# brain.net
KiCad netlist of a schematic drawn in Altium Designer
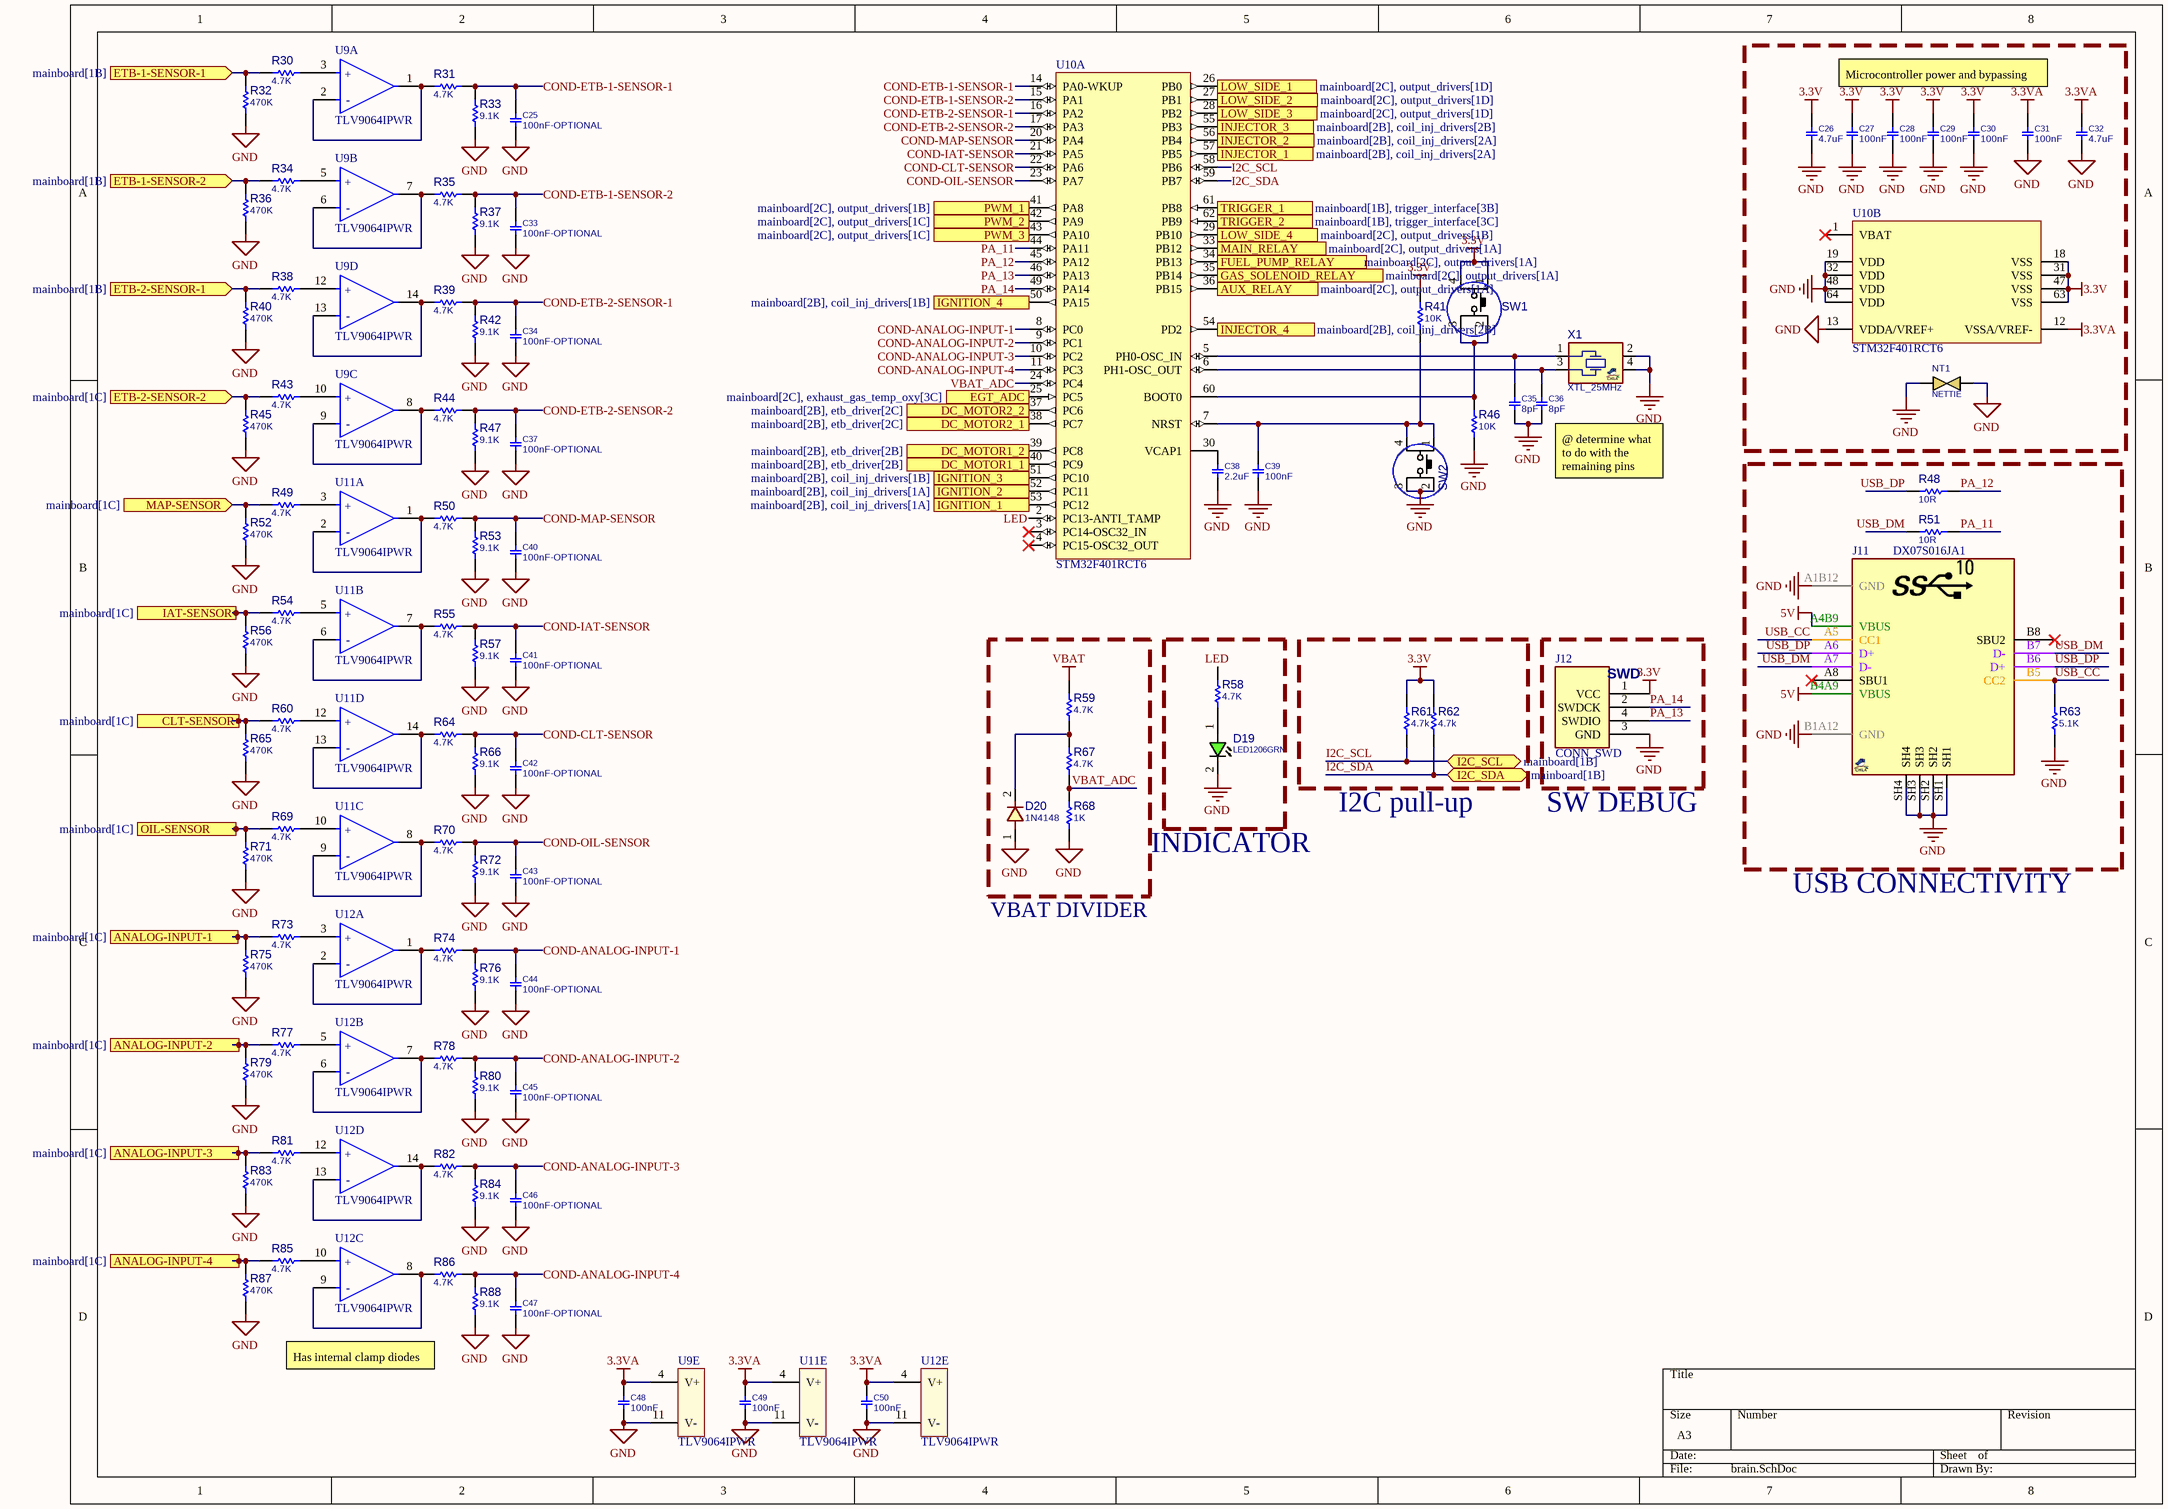
[diagram p0: brain.SchDoc]

(export (version "E")
  (design (tool "Eeschema 10.0.6"))
  (components
    (comp (ref "C25")
      (value "100nF-OPTIONAL")
      (footprint "C0805")
      (description "CAP, MLCC")
      (fields (field (name "MANF_P#") "MANF_PART#") (field (name "MANF") "Murata"))
      (libsource (lib "passive_smd") (part "CAP_SMD_MLCC"))
    )
    (comp (ref "C26")
      (value "4.7uF")
      (footprint "C0805")
      (description "CAP, MLCC")
      (fields (field (name "MANF_P#") "MANF_PART#") (field (name "MANF") "Murata"))
      (libsource (lib "passive_smd") (part "CAP_SMD_MLCC"))
    )
    (comp (ref "C27")
      (value "100nF")
      (footprint "C0805")
      (description "CAP, MLCC")
      (fields (field (name "MANF_P#") "MANF_PART#") (field (name "MANF") "Murata"))
      (libsource (lib "passive_smd") (part "CAP_SMD_MLCC"))
    )
    (comp (ref "C28")
      (value "100nF")
      (footprint "C0805")
      (description "CAP, MLCC")
      (fields (field (name "MANF_P#") "MANF_PART#") (field (name "MANF") "Murata"))
      (libsource (lib "passive_smd") (part "CAP_SMD_MLCC"))
    )
    (comp (ref "C29")
      (value "100nF")
      (footprint "C0805")
      (description "CAP, MLCC")
      (fields (field (name "MANF_P#") "MANF_PART#") (field (name "MANF") "Murata"))
      (libsource (lib "passive_smd") (part "CAP_SMD_MLCC"))
    )
    (comp (ref "C30")
      (value "100nF")
      (footprint "C0805")
      (description "CAP, MLCC")
      (fields (field (name "MANF_P#") "MANF_PART#") (field (name "MANF") "Murata"))
      (libsource (lib "passive_smd") (part "CAP_SMD_MLCC"))
    )
    (comp (ref "C31")
      (value "100nF")
      (footprint "C0805")
      (description "CAP, MLCC")
      (fields (field (name "MANF_P#") "MANF_PART#") (field (name "MANF") "Murata"))
      (libsource (lib "passive_smd") (part "CAP_SMD_MLCC"))
    )
    (comp (ref "C32")
      (value "4.7uF")
      (footprint "C0805")
      (description "CAP, MLCC")
      (fields (field (name "MANF_P#") "MANF_PART#") (field (name "MANF") "Murata"))
      (libsource (lib "passive_smd") (part "CAP_SMD_MLCC"))
    )
    (comp (ref "C33")
      (value "100nF-OPTIONAL")
      (footprint "C0805")
      (description "CAP, MLCC")
      (fields (field (name "MANF_P#") "MANF_PART#") (field (name "MANF") "Murata"))
      (libsource (lib "passive_smd") (part "CAP_SMD_MLCC"))
    )
    (comp (ref "C34")
      (value "100nF-OPTIONAL")
      (footprint "C0805")
      (description "CAP, MLCC")
      (fields (field (name "MANF_P#") "MANF_PART#") (field (name "MANF") "Murata"))
      (libsource (lib "passive_smd") (part "CAP_SMD_MLCC"))
    )
    (comp (ref "C35")
      (value "8pF")
      (footprint "C0805")
      (description "CAP, MLCC")
      (fields (field (name "MANF_P#") "MANF_PART#") (field (name "MANF") "Murata"))
      (libsource (lib "passive_smd") (part "CAP_SMD_MLCC"))
    )
    (comp (ref "C36")
      (value "8pF")
      (footprint "C0805")
      (description "CAP, MLCC")
      (fields (field (name "MANF_P#") "MANF_PART#") (field (name "MANF") "Murata"))
      (libsource (lib "passive_smd") (part "CAP_SMD_MLCC"))
    )
    (comp (ref "C37")
      (value "100nF-OPTIONAL")
      (footprint "C0805")
      (description "CAP, MLCC")
      (fields (field (name "MANF_P#") "MANF_PART#") (field (name "MANF") "Murata"))
      (libsource (lib "passive_smd") (part "CAP_SMD_MLCC"))
    )
    (comp (ref "C38")
      (value "2.2uF")
      (footprint "C0805")
      (description "CAP, MLCC")
      (fields (field (name "MANF_P#") "MANF_PART#") (field (name "MANF") "Murata"))
      (libsource (lib "passive_smd") (part "CAP_SMD_MLCC"))
    )
    (comp (ref "C39")
      (value "100nF")
      (footprint "C0805")
      (description "CAP, MLCC")
      (fields (field (name "MANF_P#") "MANF_PART#") (field (name "MANF") "Murata"))
      (libsource (lib "passive_smd") (part "CAP_SMD_MLCC"))
    )
    (comp (ref "C40")
      (value "100nF-OPTIONAL")
      (footprint "C0805")
      (description "CAP, MLCC")
      (fields (field (name "MANF_P#") "MANF_PART#") (field (name "MANF") "Murata"))
      (libsource (lib "passive_smd") (part "CAP_SMD_MLCC"))
    )
    (comp (ref "C41")
      (value "100nF-OPTIONAL")
      (footprint "C0805")
      (description "CAP, MLCC")
      (fields (field (name "MANF_P#") "MANF_PART#") (field (name "MANF") "Murata"))
      (libsource (lib "passive_smd") (part "CAP_SMD_MLCC"))
    )
    (comp (ref "C42")
      (value "100nF-OPTIONAL")
      (footprint "C0805")
      (description "CAP, MLCC")
      (fields (field (name "MANF_P#") "MANF_PART#") (field (name "MANF") "Murata"))
      (libsource (lib "passive_smd") (part "CAP_SMD_MLCC"))
    )
    (comp (ref "C43")
      (value "100nF-OPTIONAL")
      (footprint "C0805")
      (description "CAP, MLCC")
      (fields (field (name "MANF_P#") "MANF_PART#") (field (name "MANF") "Murata"))
      (libsource (lib "passive_smd") (part "CAP_SMD_MLCC"))
    )
    (comp (ref "C44")
      (value "100nF-OPTIONAL")
      (footprint "C0805")
      (description "CAP, MLCC")
      (fields (field (name "MANF_P#") "MANF_PART#") (field (name "MANF") "Murata"))
      (libsource (lib "passive_smd") (part "CAP_SMD_MLCC"))
    )
    (comp (ref "C45")
      (value "100nF-OPTIONAL")
      (footprint "C0805")
      (description "CAP, MLCC")
      (fields (field (name "MANF_P#") "MANF_PART#") (field (name "MANF") "Murata"))
      (libsource (lib "passive_smd") (part "CAP_SMD_MLCC"))
    )
    (comp (ref "C46")
      (value "100nF-OPTIONAL")
      (footprint "C0805")
      (description "CAP, MLCC")
      (fields (field (name "MANF_P#") "MANF_PART#") (field (name "MANF") "Murata"))
      (libsource (lib "passive_smd") (part "CAP_SMD_MLCC"))
    )
    (comp (ref "C47")
      (value "100nF-OPTIONAL")
      (footprint "C0805")
      (description "CAP, MLCC")
      (fields (field (name "MANF_P#") "MANF_PART#") (field (name "MANF") "Murata"))
      (libsource (lib "passive_smd") (part "CAP_SMD_MLCC"))
    )
    (comp (ref "C48")
      (value "100nF")
      (footprint "C0805")
      (description "CAP, MLCC")
      (fields (field (name "MANF_P#") "MANF_PART#") (field (name "MANF") "Murata"))
      (libsource (lib "passive_smd") (part "CAP_SMD_MLCC"))
    )
    (comp (ref "C49")
      (value "100nF")
      (footprint "C0805")
      (description "CAP, MLCC")
      (fields (field (name "MANF_P#") "MANF_PART#") (field (name "MANF") "Murata"))
      (libsource (lib "passive_smd") (part "CAP_SMD_MLCC"))
    )
    (comp (ref "C50")
      (value "100nF")
      (footprint "C0805")
      (description "CAP, MLCC")
      (fields (field (name "MANF_P#") "MANF_PART#") (field (name "MANF") "Murata"))
      (libsource (lib "passive_smd") (part "CAP_SMD_MLCC"))
    )
    (comp (ref "D19")
      (value "LED1206GRN")
      (footprint "LED1206GRN")
      (description "LED, SMD, 1206, GREEN")
      (libsource (lib "led(diode)") (part "LED_SMD_1206_GRN"))
    )
    (comp (ref "D20")
      (value "1N4148")
      (footprint "D_SOD80")
      (description "DIODE, FAST SWTICHING, 0.3A, 0.5W")
      (fields (field (name "MANF") "MANF"))
      (libsource (lib "diode") (part "DIODE_SMD_1N4148_SOD80"))
    )
    (comp (ref "J11")
      (value "DX07S016JA1")
      (footprint "USBC_SMD_16_DX07S016JA1")
      (description "CONN, USB, Type C, USB 2.0, Right-Angle, SMD")
      (fields (field (name "MANF") "JAE") (field (name "MANF_P#") "DX07S016JA1R1500"))
      (libsource (lib "conn_usbc") (part "CONN_USBC_SMD_16_DX07S016JA1"))
    )
    (comp (ref "J12")
      (value "CONN_SWD")
      (footprint "WF_4")
      (description "CONN, SWD, ST")
      (libsource (lib "conn_program") (part "CONN_SWD"))
    )
    (comp (ref "NT1")
      (value "NETTIE")
      (footprint "NETTIE_40X50")
      (description "NET TIE")
      (libsource (lib "test-tp_jumper") (part "NETTIE_40X50"))
    )
    (comp (ref "R30")
      (value "4.7K")
      (footprint "R0805")
      (description "RESISTOR, SMD")
      (libsource (lib "passive_smd") (part "RES_SMD"))
    )
    (comp (ref "R31")
      (value "4.7K")
      (footprint "R0805")
      (description "RESISTOR, SMD")
      (libsource (lib "passive_smd") (part "RES_SMD"))
    )
    (comp (ref "R32")
      (value "470K")
      (footprint "R0805")
      (description "RESISTOR, SMD")
      (libsource (lib "passive_smd") (part "RES_SMD"))
    )
    (comp (ref "R33")
      (value "9.1K")
      (footprint "R0805")
      (description "RESISTOR, SMD")
      (libsource (lib "passive_smd") (part "RES_SMD"))
    )
    (comp (ref "R34")
      (value "4.7K")
      (footprint "R0805")
      (description "RESISTOR, SMD")
      (libsource (lib "passive_smd") (part "RES_SMD"))
    )
    (comp (ref "R35")
      (value "4.7K")
      (footprint "R0805")
      (description "RESISTOR, SMD")
      (libsource (lib "passive_smd") (part "RES_SMD"))
    )
    (comp (ref "R36")
      (value "470K")
      (footprint "R0805")
      (description "RESISTOR, SMD")
      (libsource (lib "passive_smd") (part "RES_SMD"))
    )
    (comp (ref "R37")
      (value "9.1K")
      (footprint "R0805")
      (description "RESISTOR, SMD")
      (libsource (lib "passive_smd") (part "RES_SMD"))
    )
    (comp (ref "R38")
      (value "4.7K")
      (footprint "R0805")
      (description "RESISTOR, SMD")
      (libsource (lib "passive_smd") (part "RES_SMD"))
    )
    (comp (ref "R39")
      (value "4.7K")
      (footprint "R0805")
      (description "RESISTOR, SMD")
      (libsource (lib "passive_smd") (part "RES_SMD"))
    )
    (comp (ref "R40")
      (value "470K")
      (footprint "R0805")
      (description "RESISTOR, SMD")
      (libsource (lib "passive_smd") (part "RES_SMD"))
    )
    (comp (ref "R41")
      (value "10K")
      (footprint "R0805")
      (description "RESISTOR, SMD")
      (libsource (lib "passive_smd") (part "RES_SMD"))
    )
    (comp (ref "R42")
      (value "9.1K")
      (footprint "R0805")
      (description "RESISTOR, SMD")
      (libsource (lib "passive_smd") (part "RES_SMD"))
    )
    (comp (ref "R43")
      (value "4.7K")
      (footprint "R0805")
      (description "RESISTOR, SMD")
      (libsource (lib "passive_smd") (part "RES_SMD"))
    )
    (comp (ref "R44")
      (value "4.7K")
      (footprint "R0805")
      (description "RESISTOR, SMD")
      (libsource (lib "passive_smd") (part "RES_SMD"))
    )
    (comp (ref "R45")
      (value "470K")
      (footprint "R0805")
      (description "RESISTOR, SMD")
      (libsource (lib "passive_smd") (part "RES_SMD"))
    )
    (comp (ref "R46")
      (value "10K")
      (footprint "R0805")
      (description "RESISTOR, SMD")
      (libsource (lib "passive_smd") (part "RES_SMD"))
    )
    (comp (ref "R47")
      (value "9.1K")
      (footprint "R0805")
      (description "RESISTOR, SMD")
      (libsource (lib "passive_smd") (part "RES_SMD"))
    )
    (comp (ref "R48")
      (value "10R")
      (footprint "R0805")
      (description "RESISTOR, SMD")
      (libsource (lib "passive_smd") (part "RES_SMD_0805"))
    )
    (comp (ref "R49")
      (value "4.7K")
      (footprint "R0805")
      (description "RESISTOR, SMD")
      (libsource (lib "passive_smd") (part "RES_SMD"))
    )
    (comp (ref "R50")
      (value "4.7K")
      (footprint "R0805")
      (description "RESISTOR, SMD")
      (libsource (lib "passive_smd") (part "RES_SMD"))
    )
    (comp (ref "R51")
      (value "10R")
      (footprint "R0805")
      (description "RESISTOR, SMD")
      (libsource (lib "passive_smd") (part "RES_SMD_0805"))
    )
    (comp (ref "R52")
      (value "470K")
      (footprint "R0805")
      (description "RESISTOR, SMD")
      (libsource (lib "passive_smd") (part "RES_SMD"))
    )
    (comp (ref "R53")
      (value "9.1K")
      (footprint "R0805")
      (description "RESISTOR, SMD")
      (libsource (lib "passive_smd") (part "RES_SMD"))
    )
    (comp (ref "R54")
      (value "4.7K")
      (footprint "R0805")
      (description "RESISTOR, SMD")
      (libsource (lib "passive_smd") (part "RES_SMD"))
    )
    (comp (ref "R55")
      (value "4.7K")
      (footprint "R0805")
      (description "RESISTOR, SMD")
      (libsource (lib "passive_smd") (part "RES_SMD"))
    )
    (comp (ref "R56")
      (value "470K")
      (footprint "R0805")
      (description "RESISTOR, SMD")
      (libsource (lib "passive_smd") (part "RES_SMD"))
    )
    (comp (ref "R57")
      (value "9.1K")
      (footprint "R0805")
      (description "RESISTOR, SMD")
      (libsource (lib "passive_smd") (part "RES_SMD"))
    )
    (comp (ref "R58")
      (value "4.7K")
      (footprint "R0805")
      (description "RESISTOR, SMD")
      (libsource (lib "passive_smd") (part "RES_SMD"))
    )
    (comp (ref "R59")
      (value "4.7K")
      (footprint "R0805")
      (description "RESISTOR, SMD")
      (libsource (lib "passive_smd") (part "RES_SMD"))
    )
    (comp (ref "R60")
      (value "4.7K")
      (footprint "R0805")
      (description "RESISTOR, SMD")
      (libsource (lib "passive_smd") (part "RES_SMD"))
    )
    (comp (ref "R61")
      (value "4.7k")
      (footprint "R0805")
      (description "RESISTOR, SMD")
      (libsource (lib "passive_smd") (part "RES_SMD"))
    )
    (comp (ref "R62")
      (value "4.7k")
      (footprint "R0805")
      (description "RESISTOR, SMD")
      (libsource (lib "passive_smd") (part "RES_SMD"))
    )
    (comp (ref "R63")
      (value "5.1K")
      (footprint "R1206")
      (description "RESISTOR, SMD")
      (libsource (lib "passive_smd") (part "RES_SMD_1206"))
    )
    (comp (ref "R64")
      (value "4.7K")
      (footprint "R0805")
      (description "RESISTOR, SMD")
      (libsource (lib "passive_smd") (part "RES_SMD"))
    )
    (comp (ref "R65")
      (value "470K")
      (footprint "R0805")
      (description "RESISTOR, SMD")
      (libsource (lib "passive_smd") (part "RES_SMD"))
    )
    (comp (ref "R66")
      (value "9.1K")
      (footprint "R0805")
      (description "RESISTOR, SMD")
      (libsource (lib "passive_smd") (part "RES_SMD"))
    )
    (comp (ref "R67")
      (value "4.7K")
      (footprint "R0805")
      (description "RESISTOR, SMD")
      (libsource (lib "passive_smd") (part "RES_SMD"))
    )
    (comp (ref "R68")
      (value "1K")
      (footprint "R0805")
      (description "RESISTOR, SMD")
      (libsource (lib "passive_smd") (part "RES_SMD"))
    )
    (comp (ref "R69")
      (value "4.7K")
      (footprint "R0805")
      (description "RESISTOR, SMD")
      (libsource (lib "passive_smd") (part "RES_SMD"))
    )
    (comp (ref "R70")
      (value "4.7K")
      (footprint "R0805")
      (description "RESISTOR, SMD")
      (libsource (lib "passive_smd") (part "RES_SMD"))
    )
    (comp (ref "R71")
      (value "470K")
      (footprint "R0805")
      (description "RESISTOR, SMD")
      (libsource (lib "passive_smd") (part "RES_SMD"))
    )
    (comp (ref "R72")
      (value "9.1K")
      (footprint "R0805")
      (description "RESISTOR, SMD")
      (libsource (lib "passive_smd") (part "RES_SMD"))
    )
    (comp (ref "R73")
      (value "4.7K")
      (footprint "R0805")
      (description "RESISTOR, SMD")
      (libsource (lib "passive_smd") (part "RES_SMD"))
    )
    (comp (ref "R74")
      (value "4.7K")
      (footprint "R0805")
      (description "RESISTOR, SMD")
      (libsource (lib "passive_smd") (part "RES_SMD"))
    )
    (comp (ref "R75")
      (value "470K")
      (footprint "R0805")
      (description "RESISTOR, SMD")
      (libsource (lib "passive_smd") (part "RES_SMD"))
    )
    (comp (ref "R76")
      (value "9.1K")
      (footprint "R0805")
      (description "RESISTOR, SMD")
      (libsource (lib "passive_smd") (part "RES_SMD"))
    )
    (comp (ref "R77")
      (value "4.7K")
      (footprint "R0805")
      (description "RESISTOR, SMD")
      (libsource (lib "passive_smd") (part "RES_SMD"))
    )
    (comp (ref "R78")
      (value "4.7K")
      (footprint "R0805")
      (description "RESISTOR, SMD")
      (libsource (lib "passive_smd") (part "RES_SMD"))
    )
    (comp (ref "R79")
      (value "470K")
      (footprint "R0805")
      (description "RESISTOR, SMD")
      (libsource (lib "passive_smd") (part "RES_SMD"))
    )
    (comp (ref "R80")
      (value "9.1K")
      (footprint "R0805")
      (description "RESISTOR, SMD")
      (libsource (lib "passive_smd") (part "RES_SMD"))
    )
    (comp (ref "R81")
      (value "4.7K")
      (footprint "R0805")
      (description "RESISTOR, SMD")
      (libsource (lib "passive_smd") (part "RES_SMD"))
    )
    (comp (ref "R82")
      (value "4.7K")
      (footprint "R0805")
      (description "RESISTOR, SMD")
      (libsource (lib "passive_smd") (part "RES_SMD"))
    )
    (comp (ref "R83")
      (value "470K")
      (footprint "R0805")
      (description "RESISTOR, SMD")
      (libsource (lib "passive_smd") (part "RES_SMD"))
    )
    (comp (ref "R84")
      (value "9.1K")
      (footprint "R0805")
      (description "RESISTOR, SMD")
      (libsource (lib "passive_smd") (part "RES_SMD"))
    )
    (comp (ref "R85")
      (value "4.7K")
      (footprint "R0805")
      (description "RESISTOR, SMD")
      (libsource (lib "passive_smd") (part "RES_SMD"))
    )
    (comp (ref "R86")
      (value "4.7K")
      (footprint "R0805")
      (description "RESISTOR, SMD")
      (libsource (lib "passive_smd") (part "RES_SMD"))
    )
    (comp (ref "R87")
      (value "470K")
      (footprint "R0805")
      (description "RESISTOR, SMD")
      (libsource (lib "passive_smd") (part "RES_SMD"))
    )
    (comp (ref "R88")
      (value "9.1K")
      (footprint "R0805")
      (description "RESISTOR, SMD")
      (libsource (lib "passive_smd") (part "RES_SMD"))
    )
    (comp (ref "SW1")
      (value "PUSHBUTTON")
      (footprint "SWPBS_SPDT_5X5X1")
      (description "SWITCH, PUSH BUTTON, TACTILE, SMD, SPDT, 5X5MM")
      (fields (field (name "MANF") "CHINA") (field (name "MANF_P#") "PTS526SM15SMTR2LFS"))
      (libsource (lib "switch_tact_PUSHB") (part "SWPBS_SPDT_5X5PTS"))
    )
    (comp (ref "SW2")
      (value "PUSHBUTTON")
      (footprint "SWPBS_SPDT_5X5X1")
      (description "SWITCH, PUSH BUTTON, TACTILE, SMD, SPDT, 5X5MM")
      (fields (field (name "MANF") "CHINA") (field (name "MANF_P#") "PTS526SM15SMTR2LFS"))
      (libsource (lib "switch_tact_PUSHB") (part "SWPBS_SPDT_5X5PTS"))
    )
    (comp (ref "U9")
      (value "TLV9064IPWR")
      (footprint "TTSOP-14")
      (description "IC CMOS 4 CIRCUIT 14TSSOP")
      (libsource (lib "alib") (part "TLV9064"))
    )
    (comp (ref "U10")
      (value "STM32F401RCT6")
      (footprint "STM-LQFP64_L")
      (fields (field (name "MANUFACTURER") "STMicroelectronics"))
      (libsource (lib "Alib") (part "STM32F401RCT6"))
    )
    (comp (ref "U11")
      (value "TLV9064IPWR")
      (footprint "TTSOP-14")
      (description "IC CMOS 4 CIRCUIT 14TSSOP")
      (libsource (lib "alib") (part "TLV9064"))
    )
    (comp (ref "U12")
      (value "TLV9064IPWR")
      (footprint "TTSOP-14")
      (description "IC CMOS 4 CIRCUIT 14TSSOP")
      (libsource (lib "alib") (part "TLV9064"))
    )
    (comp (ref "X1")
      (value "XTL_25MHz")
      (footprint "XTL_4_3225")
      (description "CRYSTAL 25.00 MHZ 4pF, 10PPM")
      (fields (field (name "MANF") "ABRACON") (field (name "MANF_P#") "ABM8W-25.0000MHZ-4-D1X-T3"))
      (libsource (lib "crystal") (part "XTL_4_25MHZ_3225A_2"))
    )
  )
  (nets
    (net (code "1") (name "/ANALOG-INPUT-1") (class "Default")
      (node (ref "R73") (pin "2") (pinfunction "2_2") (pintype "passive"))
      (node (ref "R75") (pin "1") (pinfunction "1_1") (pintype "passive"))
    )
    (net (code "2") (name "/ANALOG-INPUT-2") (class "Default")
      (node (ref "R77") (pin "2") (pinfunction "2_2") (pintype "passive"))
      (node (ref "R79") (pin "1") (pinfunction "1_1") (pintype "passive"))
    )
    (net (code "3") (name "/ANALOG-INPUT-3") (class "Default")
      (node (ref "R81") (pin "2") (pinfunction "2_2") (pintype "passive"))
      (node (ref "R83") (pin "1") (pinfunction "1_1") (pintype "passive"))
    )
    (net (code "4") (name "/ANALOG-INPUT-4") (class "Default")
      (node (ref "R85") (pin "2") (pinfunction "2_2") (pintype "passive"))
      (node (ref "R87") (pin "1") (pinfunction "1_1") (pintype "passive"))
    )
    (net (code "5") (name "/AUX_RELAY") (class "Default")
      (node (ref "U10") (pin "36") (pinfunction "PB15_36") (pintype "output"))
    )
    (net (code "6") (name "/CLT-SENSOR") (class "Default")
      (node (ref "R60") (pin "2") (pinfunction "2_2") (pintype "passive"))
      (node (ref "R65") (pin "1") (pinfunction "1_1") (pintype "passive"))
    )
    (net (code "7") (name "/COND-ANALOG-INPUT-1") (class "Default")
      (node (ref "C44") (pin "2") (pinfunction "2_2") (pintype "passive"))
      (node (ref "R74") (pin "1") (pinfunction "1_1") (pintype "passive"))
      (node (ref "R76") (pin "1") (pinfunction "1_1") (pintype "passive"))
      (node (ref "U10") (pin "8") (pinfunction "PC0_8") (pintype "bidirectional"))
    )
    (net (code "8") (name "/COND-ANALOG-INPUT-2") (class "Default")
      (node (ref "C45") (pin "2") (pinfunction "2_2") (pintype "passive"))
      (node (ref "R78") (pin "1") (pinfunction "1_1") (pintype "passive"))
      (node (ref "R80") (pin "1") (pinfunction "1_1") (pintype "passive"))
      (node (ref "U10") (pin "9") (pinfunction "PC1_9") (pintype "bidirectional"))
    )
    (net (code "9") (name "/COND-ANALOG-INPUT-3") (class "Default")
      (node (ref "C46") (pin "2") (pinfunction "2_2") (pintype "passive"))
      (node (ref "R82") (pin "1") (pinfunction "1_1") (pintype "passive"))
      (node (ref "R84") (pin "1") (pinfunction "1_1") (pintype "passive"))
      (node (ref "U10") (pin "10") (pinfunction "PC2_10") (pintype "bidirectional"))
    )
    (net (code "10") (name "/COND-ANALOG-INPUT-4") (class "Default")
      (node (ref "C47") (pin "2") (pinfunction "2_2") (pintype "passive"))
      (node (ref "R86") (pin "1") (pinfunction "1_1") (pintype "passive"))
      (node (ref "R88") (pin "1") (pinfunction "1_1") (pintype "passive"))
      (node (ref "U10") (pin "11") (pinfunction "PC3_11") (pintype "bidirectional"))
    )
    (net (code "11") (name "/COND-CLT-SENSOR") (class "Default")
      (node (ref "C42") (pin "2") (pinfunction "2_2") (pintype "passive"))
      (node (ref "R64") (pin "1") (pinfunction "1_1") (pintype "passive"))
      (node (ref "R66") (pin "1") (pinfunction "1_1") (pintype "passive"))
      (node (ref "U10") (pin "22") (pinfunction "PA6_22") (pintype "bidirectional"))
    )
    (net (code "12") (name "/COND-ETB-1-SENSOR-1") (class "Default")
      (node (ref "C25") (pin "2") (pinfunction "2_2") (pintype "passive"))
      (node (ref "R31") (pin "1") (pinfunction "1_1") (pintype "passive"))
      (node (ref "R33") (pin "1") (pinfunction "1_1") (pintype "passive"))
      (node (ref "U10") (pin "14") (pinfunction "PA0-WKUP_14") (pintype "bidirectional"))
    )
    (net (code "13") (name "/COND-ETB-1-SENSOR-2") (class "Default")
      (node (ref "C33") (pin "2") (pinfunction "2_2") (pintype "passive"))
      (node (ref "R35") (pin "1") (pinfunction "1_1") (pintype "passive"))
      (node (ref "R37") (pin "1") (pinfunction "1_1") (pintype "passive"))
      (node (ref "U10") (pin "15") (pinfunction "PA1_15") (pintype "bidirectional"))
    )
    (net (code "14") (name "/COND-ETB-2-SENSOR-1") (class "Default")
      (node (ref "C34") (pin "2") (pinfunction "2_2") (pintype "passive"))
      (node (ref "R39") (pin "1") (pinfunction "1_1") (pintype "passive"))
      (node (ref "R42") (pin "1") (pinfunction "1_1") (pintype "passive"))
      (node (ref "U10") (pin "16") (pinfunction "PA2_16") (pintype "bidirectional"))
    )
    (net (code "15") (name "/COND-ETB-2-SENSOR-2") (class "Default")
      (node (ref "C37") (pin "2") (pinfunction "2_2") (pintype "passive"))
      (node (ref "R44") (pin "1") (pinfunction "1_1") (pintype "passive"))
      (node (ref "R47") (pin "1") (pinfunction "1_1") (pintype "passive"))
      (node (ref "U10") (pin "17") (pinfunction "PA3_17") (pintype "bidirectional"))
    )
    (net (code "16") (name "/COND-IAT-SENSOR") (class "Default")
      (node (ref "C41") (pin "2") (pinfunction "2_2") (pintype "passive"))
      (node (ref "R55") (pin "1") (pinfunction "1_1") (pintype "passive"))
      (node (ref "R57") (pin "1") (pinfunction "1_1") (pintype "passive"))
      (node (ref "U10") (pin "21") (pinfunction "PA5_21") (pintype "bidirectional"))
    )
    (net (code "17") (name "/COND-MAP-SENSOR") (class "Default")
      (node (ref "C40") (pin "2") (pinfunction "2_2") (pintype "passive"))
      (node (ref "R50") (pin "1") (pinfunction "1_1") (pintype "passive"))
      (node (ref "R53") (pin "1") (pinfunction "1_1") (pintype "passive"))
      (node (ref "U10") (pin "20") (pinfunction "PA4_20") (pintype "bidirectional"))
    )
    (net (code "18") (name "/COND-OIL-SENSOR") (class "Default")
      (node (ref "C43") (pin "2") (pinfunction "2_2") (pintype "passive"))
      (node (ref "R70") (pin "1") (pinfunction "1_1") (pintype "passive"))
      (node (ref "R72") (pin "1") (pinfunction "1_1") (pintype "passive"))
      (node (ref "U10") (pin "23") (pinfunction "PA7_23") (pintype "bidirectional"))
    )
    (net (code "19") (name "/DC_MOTOR1_1") (class "Default")
      (node (ref "U10") (pin "40") (pinfunction "PC9_40") (pintype "output"))
    )
    (net (code "20") (name "/DC_MOTOR1_2") (class "Default")
      (node (ref "U10") (pin "39") (pinfunction "PC8_39") (pintype "output"))
    )
    (net (code "21") (name "/DC_MOTOR2_1") (class "Default")
      (node (ref "U10") (pin "38") (pinfunction "PC7_38") (pintype "output"))
    )
    (net (code "22") (name "/DC_MOTOR2_2") (class "Default")
      (node (ref "U10") (pin "37") (pinfunction "PC6_37") (pintype "output"))
    )
    (net (code "23") (name "/EGT_ADC") (class "Default")
      (node (ref "U10") (pin "25") (pinfunction "PC5_25") (pintype "input"))
    )
    (net (code "24") (name "/ETB-1-SENSOR-1") (class "Default")
      (node (ref "R30") (pin "2") (pinfunction "2_2") (pintype "passive"))
      (node (ref "R32") (pin "1") (pinfunction "1_1") (pintype "passive"))
    )
    (net (code "25") (name "/ETB-1-SENSOR-2") (class "Default")
      (node (ref "R34") (pin "2") (pinfunction "2_2") (pintype "passive"))
      (node (ref "R36") (pin "1") (pinfunction "1_1") (pintype "passive"))
    )
    (net (code "26") (name "/ETB-2-SENSOR-1") (class "Default")
      (node (ref "R38") (pin "2") (pinfunction "2_2") (pintype "passive"))
      (node (ref "R40") (pin "1") (pinfunction "1_1") (pintype "passive"))
    )
    (net (code "27") (name "/ETB-2-SENSOR-2") (class "Default")
      (node (ref "R43") (pin "2") (pinfunction "2_2") (pintype "passive"))
      (node (ref "R45") (pin "1") (pinfunction "1_1") (pintype "passive"))
    )
    (net (code "28") (name "/FUEL_PUMP_RELAY") (class "Default")
      (node (ref "U10") (pin "34") (pinfunction "PB13_34") (pintype "output"))
    )
    (net (code "29") (name "/GAS_SOLENOID_RELAY") (class "Default")
      (node (ref "U10") (pin "35") (pinfunction "PB14_35") (pintype "output"))
    )
    (net (code "30") (name "/I2C_SCL") (class "Default")
      (node (ref "R61") (pin "1") (pinfunction "1_1") (pintype "passive"))
      (node (ref "U10") (pin "58") (pinfunction "PB6_58") (pintype "bidirectional"))
    )
    (net (code "31") (name "/I2C_SDA") (class "Default")
      (node (ref "R62") (pin "1") (pinfunction "1_1") (pintype "passive"))
      (node (ref "U10") (pin "59") (pinfunction "PB7_59") (pintype "bidirectional"))
    )
    (net (code "32") (name "/IAT-SENSOR") (class "Default")
      (node (ref "R54") (pin "2") (pinfunction "2_2") (pintype "passive"))
      (node (ref "R56") (pin "1") (pinfunction "1_1") (pintype "passive"))
    )
    (net (code "33") (name "/IGNITION_1") (class "Default")
      (node (ref "U10") (pin "53") (pinfunction "PC12_53") (pintype "output"))
    )
    (net (code "34") (name "/IGNITION_2") (class "Default")
      (node (ref "U10") (pin "52") (pinfunction "PC11_52") (pintype "output"))
    )
    (net (code "35") (name "/IGNITION_3") (class "Default")
      (node (ref "U10") (pin "51") (pinfunction "PC10_51") (pintype "output"))
    )
    (net (code "36") (name "/IGNITION_4") (class "Default")
      (node (ref "U10") (pin "50") (pinfunction "PA15_50") (pintype "output"))
    )
    (net (code "37") (name "/INJECTOR_1") (class "Default")
      (node (ref "U10") (pin "57") (pinfunction "PB5_57") (pintype "output"))
    )
    (net (code "38") (name "/INJECTOR_2") (class "Default")
      (node (ref "U10") (pin "56") (pinfunction "PB4_56") (pintype "output"))
    )
    (net (code "39") (name "/INJECTOR_3") (class "Default")
      (node (ref "U10") (pin "55") (pinfunction "PB3_55") (pintype "output"))
    )
    (net (code "40") (name "/INJECTOR_4") (class "Default")
      (node (ref "U10") (pin "54") (pinfunction "PD2_54") (pintype "output"))
    )
    (net (code "41") (name "/LED") (class "Default")
      (node (ref "R58") (pin "2") (pinfunction "2_2") (pintype "passive"))
      (node (ref "U10") (pin "2") (pinfunction "PC13-ANTI_TAMP_2") (pintype "bidirectional"))
    )
    (net (code "42") (name "/LOW_SIDE_1") (class "Default")
      (node (ref "U10") (pin "26") (pinfunction "PB0_26") (pintype "output"))
    )
    (net (code "43") (name "/LOW_SIDE_2") (class "Default")
      (node (ref "U10") (pin "27") (pinfunction "PB1_27") (pintype "output"))
    )
    (net (code "44") (name "/LOW_SIDE_3") (class "Default")
      (node (ref "U10") (pin "28") (pinfunction "PB2_28") (pintype "output"))
    )
    (net (code "45") (name "/LOW_SIDE_4") (class "Default")
      (node (ref "U10") (pin "29") (pinfunction "PB10_29") (pintype "output"))
    )
    (net (code "46") (name "/MAIN_RELAY") (class "Default")
      (node (ref "U10") (pin "33") (pinfunction "PB12_33") (pintype "output"))
    )
    (net (code "47") (name "/MAP-SENSOR") (class "Default")
      (node (ref "R49") (pin "2") (pinfunction "2_2") (pintype "passive"))
      (node (ref "R52") (pin "1") (pinfunction "1_1") (pintype "passive"))
    )
    (net (code "48") (name "/OIL-SENSOR") (class "Default")
      (node (ref "R69") (pin "2") (pinfunction "2_2") (pintype "passive"))
      (node (ref "R71") (pin "1") (pinfunction "1_1") (pintype "passive"))
    )
    (net (code "49") (name "/PA_11") (class "Default")
      (node (ref "R51") (pin "1") (pinfunction "1_1") (pintype "passive"))
      (node (ref "U10") (pin "44") (pinfunction "PA11_44") (pintype "bidirectional"))
    )
    (net (code "50") (name "/PA_12") (class "Default")
      (node (ref "R48") (pin "1") (pinfunction "1_1") (pintype "passive"))
      (node (ref "U10") (pin "45") (pinfunction "PA12_45") (pintype "bidirectional"))
    )
    (net (code "51") (name "/PA_13") (class "Default")
      (node (ref "J12") (pin "4") (pinfunction "SWDIO_4") (pintype "passive"))
      (node (ref "U10") (pin "46") (pinfunction "PA13_46") (pintype "bidirectional"))
    )
    (net (code "52") (name "/PA_14") (class "Default")
      (node (ref "J12") (pin "2") (pinfunction "SWDCK_2") (pintype "passive"))
      (node (ref "U10") (pin "49") (pinfunction "PA14_49") (pintype "bidirectional"))
    )
    (net (code "53") (name "/PWM_1") (class "Default")
      (node (ref "U10") (pin "41") (pinfunction "PA8_41") (pintype "output"))
    )
    (net (code "54") (name "/PWM_2") (class "Default")
      (node (ref "U10") (pin "42") (pinfunction "PA9_42") (pintype "output"))
    )
    (net (code "55") (name "/PWM_3") (class "Default")
      (node (ref "U10") (pin "43") (pinfunction "PA10_43") (pintype "output"))
    )
    (net (code "56") (name "/TRIGGER_1") (class "Default")
      (node (ref "U10") (pin "61") (pinfunction "PB8_61") (pintype "input"))
    )
    (net (code "57") (name "/TRIGGER_2") (class "Default")
      (node (ref "U10") (pin "62") (pinfunction "PB9_62") (pintype "input"))
    )
    (net (code "58") (name "/USB_CC") (class "Default")
      (node (ref "J11") (pin "A5") (pinfunction "CC1_A5") (pintype "passive"))
      (node (ref "J11") (pin "B5") (pinfunction "CC2_B5") (pintype "passive"))
      (node (ref "R63") (pin "2") (pinfunction "2_2") (pintype "passive"))
    )
    (net (code "59") (name "/USB_DM") (class "Default")
      (node (ref "J11") (pin "A7") (pinfunction "D-_A7") (pintype "passive"))
      (node (ref "J11") (pin "B7") (pinfunction "D-_B7") (pintype "passive"))
      (node (ref "R51") (pin "2") (pinfunction "2_2") (pintype "passive"))
    )
    (net (code "60") (name "/USB_DP") (class "Default")
      (node (ref "J11") (pin "A6") (pinfunction "D+_A6") (pintype "passive"))
      (node (ref "J11") (pin "B6") (pinfunction "D+_B6") (pintype "passive"))
      (node (ref "R48") (pin "2") (pinfunction "2_2") (pintype "passive"))
    )
    (net (code "61") (name "/VBAT_ADC") (class "Default")
      (node (ref "R67") (pin "1") (pinfunction "1_1") (pintype "passive"))
      (node (ref "R68") (pin "2") (pinfunction "2_2") (pintype "passive"))
      (node (ref "U10") (pin "24") (pinfunction "PC4_24") (pintype "bidirectional"))
    )
    (net (code "62") (name "3.3V") (class "Default")
      (node (ref "C26") (pin "2") (pinfunction "2_2") (pintype "passive"))
      (node (ref "C27") (pin "2") (pinfunction "2_2") (pintype "passive"))
      (node (ref "C28") (pin "2") (pinfunction "2_2") (pintype "passive"))
      (node (ref "C29") (pin "2") (pinfunction "2_2") (pintype "passive"))
      (node (ref "C30") (pin "2") (pinfunction "2_2") (pintype "passive"))
      (node (ref "J12") (pin "1") (pinfunction "VCC_1") (pintype "passive"))
      (node (ref "R41") (pin "2") (pinfunction "2_2") (pintype "passive"))
      (node (ref "R61") (pin "2") (pinfunction "2_2") (pintype "passive"))
      (node (ref "R62") (pin "2") (pinfunction "2_2") (pintype "passive"))
      (node (ref "SW1") (pin "1") (pinfunction "P1_1") (pintype "passive"))
      (node (ref "SW1") (pin "4") (pinfunction "P2_4") (pintype "passive"))
      (node (ref "U10") (pin "18") (pinfunction "VSS_18") (pintype "power_in"))
      (node (ref "U10") (pin "31") (pinfunction "VSS_31") (pintype "power_in"))
      (node (ref "U10") (pin "47") (pinfunction "VSS_47") (pintype "power_in"))
      (node (ref "U10") (pin "63") (pinfunction "VSS_63") (pintype "power_in"))
    )
    (net (code "63") (name "3.3VA") (class "Default")
      (node (ref "C31") (pin "2") (pinfunction "2_2") (pintype "passive"))
      (node (ref "C32") (pin "2") (pinfunction "2_2") (pintype "passive"))
      (node (ref "C48") (pin "2") (pinfunction "2_2") (pintype "passive"))
      (node (ref "C49") (pin "2") (pinfunction "2_2") (pintype "passive"))
      (node (ref "C50") (pin "2") (pinfunction "2_2") (pintype "passive"))
      (node (ref "U10") (pin "12") (pinfunction "VSSA/VREF-_12") (pintype "power_in"))
      (node (ref "U11") (pin "4") (pinfunction "V+_4") (pintype "power_in"))
      (node (ref "U12") (pin "4") (pinfunction "V+_4") (pintype "power_in"))
      (node (ref "U9") (pin "4") (pinfunction "V+_4") (pintype "power_in"))
    )
    (net (code "64") (name "5V") (class "Default")
      (node (ref "J11") (pin "A4B9") (pinfunction "VBUS_A4B9") (pintype "passive"))
      (node (ref "J11") (pin "B4A9") (pinfunction "VBUS_B4A9") (pintype "passive"))
    )
    (net (code "65") (name "GND") (class "Default")
      (node (ref "C25") (pin "1") (pinfunction "1_1") (pintype "passive"))
      (node (ref "C26") (pin "1") (pinfunction "1_1") (pintype "passive"))
      (node (ref "C27") (pin "1") (pinfunction "1_1") (pintype "passive"))
      (node (ref "C28") (pin "1") (pinfunction "1_1") (pintype "passive"))
      (node (ref "C29") (pin "1") (pinfunction "1_1") (pintype "passive"))
      (node (ref "C30") (pin "1") (pinfunction "1_1") (pintype "passive"))
      (node (ref "C31") (pin "1") (pinfunction "1_1") (pintype "passive"))
      (node (ref "C32") (pin "1") (pinfunction "1_1") (pintype "passive"))
      (node (ref "C33") (pin "1") (pinfunction "1_1") (pintype "passive"))
      (node (ref "C34") (pin "1") (pinfunction "1_1") (pintype "passive"))
      (node (ref "C35") (pin "1") (pinfunction "1_1") (pintype "passive"))
      (node (ref "C36") (pin "1") (pinfunction "1_1") (pintype "passive"))
      (node (ref "C37") (pin "1") (pinfunction "1_1") (pintype "passive"))
      (node (ref "C38") (pin "1") (pinfunction "1_1") (pintype "passive"))
      (node (ref "C39") (pin "1") (pinfunction "1_1") (pintype "passive"))
      (node (ref "C40") (pin "1") (pinfunction "1_1") (pintype "passive"))
      (node (ref "C41") (pin "1") (pinfunction "1_1") (pintype "passive"))
      (node (ref "C42") (pin "1") (pinfunction "1_1") (pintype "passive"))
      (node (ref "C43") (pin "1") (pinfunction "1_1") (pintype "passive"))
      (node (ref "C44") (pin "1") (pinfunction "1_1") (pintype "passive"))
      (node (ref "C45") (pin "1") (pinfunction "1_1") (pintype "passive"))
      (node (ref "C46") (pin "1") (pinfunction "1_1") (pintype "passive"))
      (node (ref "C47") (pin "1") (pinfunction "1_1") (pintype "passive"))
      (node (ref "C48") (pin "1") (pinfunction "1_1") (pintype "passive"))
      (node (ref "C49") (pin "1") (pinfunction "1_1") (pintype "passive"))
      (node (ref "C50") (pin "1") (pinfunction "1_1") (pintype "passive"))
      (node (ref "D19") (pin "2") (pinfunction "CATHODE_2") (pintype "passive"))
      (node (ref "D20") (pin "1") (pinfunction "1_1") (pintype "passive"))
      (node (ref "J11") (pin "A1B12") (pinfunction "GND_A1B12") (pintype "passive"))
      (node (ref "J11") (pin "B1A12") (pinfunction "GND_B1A12") (pintype "passive"))
      (node (ref "J11") (pin "SH1") (pinfunction "SH1_SH1") (pintype "passive"))
      (node (ref "J11") (pin "SH2") (pinfunction "SH2_SH2") (pintype "passive"))
      (node (ref "J11") (pin "SH3") (pinfunction "SH3_SH3") (pintype "passive"))
      (node (ref "J11") (pin "SH4") (pinfunction "SH4_SH4") (pintype "passive"))
      (node (ref "J12") (pin "3") (pinfunction "GND_3") (pintype "passive"))
      (node (ref "NT1") (pin "1") (pinfunction "1_1") (pintype "passive"))
      (node (ref "NT1") (pin "2") (pinfunction "2_2") (pintype "passive"))
      (node (ref "R32") (pin "2") (pinfunction "2_2") (pintype "passive"))
      (node (ref "R33") (pin "2") (pinfunction "2_2") (pintype "passive"))
      (node (ref "R36") (pin "2") (pinfunction "2_2") (pintype "passive"))
      (node (ref "R37") (pin "2") (pinfunction "2_2") (pintype "passive"))
      (node (ref "R40") (pin "2") (pinfunction "2_2") (pintype "passive"))
      (node (ref "R42") (pin "2") (pinfunction "2_2") (pintype "passive"))
      (node (ref "R45") (pin "2") (pinfunction "2_2") (pintype "passive"))
      (node (ref "R46") (pin "1") (pinfunction "1_1") (pintype "passive"))
      (node (ref "R47") (pin "2") (pinfunction "2_2") (pintype "passive"))
      (node (ref "R52") (pin "2") (pinfunction "2_2") (pintype "passive"))
      (node (ref "R53") (pin "2") (pinfunction "2_2") (pintype "passive"))
      (node (ref "R56") (pin "2") (pinfunction "2_2") (pintype "passive"))
      (node (ref "R57") (pin "2") (pinfunction "2_2") (pintype "passive"))
      (node (ref "R63") (pin "1") (pinfunction "1_1") (pintype "passive"))
      (node (ref "R65") (pin "2") (pinfunction "2_2") (pintype "passive"))
      (node (ref "R66") (pin "2") (pinfunction "2_2") (pintype "passive"))
      (node (ref "R68") (pin "1") (pinfunction "1_1") (pintype "passive"))
      (node (ref "R71") (pin "2") (pinfunction "2_2") (pintype "passive"))
      (node (ref "R72") (pin "2") (pinfunction "2_2") (pintype "passive"))
      (node (ref "R75") (pin "2") (pinfunction "2_2") (pintype "passive"))
      (node (ref "R76") (pin "2") (pinfunction "2_2") (pintype "passive"))
      (node (ref "R79") (pin "2") (pinfunction "2_2") (pintype "passive"))
      (node (ref "R80") (pin "2") (pinfunction "2_2") (pintype "passive"))
      (node (ref "R83") (pin "2") (pinfunction "2_2") (pintype "passive"))
      (node (ref "R84") (pin "2") (pinfunction "2_2") (pintype "passive"))
      (node (ref "R87") (pin "2") (pinfunction "2_2") (pintype "passive"))
      (node (ref "R88") (pin "2") (pinfunction "2_2") (pintype "passive"))
      (node (ref "SW2") (pin "2") (pinfunction "P3_2") (pintype "passive"))
      (node (ref "SW2") (pin "3") (pinfunction "P4_3") (pintype "passive"))
      (node (ref "U10") (pin "13") (pinfunction "VDDA/VREF+_13") (pintype "power_in"))
      (node (ref "U10") (pin "19") (pinfunction "VDD_19") (pintype "power_in"))
      (node (ref "U10") (pin "32") (pinfunction "VDD_32") (pintype "power_in"))
      (node (ref "U10") (pin "48") (pinfunction "VDD_48") (pintype "power_in"))
      (node (ref "U10") (pin "64") (pinfunction "VDD_64") (pintype "power_in"))
      (node (ref "U11") (pin "11") (pinfunction "V-_11") (pintype "power_in"))
      (node (ref "U12") (pin "11") (pinfunction "V-_11") (pintype "power_in"))
      (node (ref "U9") (pin "11") (pinfunction "V-_11") (pintype "power_in"))
      (node (ref "X1") (pin "2") (pinfunction "2_2") (pintype "passive"))
      (node (ref "X1") (pin "4") (pinfunction "4_4") (pintype "passive"))
    )
    (net (code "66") (name "Net-(D19-ANODE)") (class "Default")
      (node (ref "D19") (pin "1") (pinfunction "ANODE_1") (pintype "passive"))
      (node (ref "R58") (pin "1") (pinfunction "1_1") (pintype "passive"))
    )
    (net (code "67") (name "Net-(D20-Pad2)") (class "Default")
      (node (ref "D20") (pin "2") (pinfunction "2_2") (pintype "passive"))
      (node (ref "R59") (pin "1") (pinfunction "1_1") (pintype "passive"))
      (node (ref "R67") (pin "2") (pinfunction "2_2") (pintype "passive"))
    )
    (net (code "68") (name "Net-(SW1-P3)") (class "Default")
      (node (ref "R46") (pin "2") (pinfunction "2_2") (pintype "passive"))
      (node (ref "SW1") (pin "2") (pinfunction "P3_2") (pintype "passive"))
      (node (ref "SW1") (pin "3") (pinfunction "P4_3") (pintype "passive"))
      (node (ref "U10") (pin "60") (pinfunction "BOOT0_60") (pintype "power_in"))
    )
    (net (code "69") (name "Net-(SW2-P1)") (class "Default")
      (node (ref "C39") (pin "2") (pinfunction "2_2") (pintype "passive"))
      (node (ref "R41") (pin "1") (pinfunction "1_1") (pintype "passive"))
      (node (ref "SW2") (pin "1") (pinfunction "P1_1") (pintype "passive"))
      (node (ref "SW2") (pin "4") (pinfunction "P2_4") (pintype "passive"))
      (node (ref "U10") (pin "7") (pinfunction "NRST_7") (pintype "bidirectional"))
    )
    (net (code "70") (name "Net-(U9A-IN1+)") (class "Default")
      (node (ref "R30") (pin "1") (pinfunction "1_1") (pintype "passive"))
      (node (ref "U9") (pin "3") (pinfunction "IN1+_3") (pintype "passive"))
    )
    (net (code "71") (name "Net-(U9A-IN1-)") (class "Default")
      (node (ref "R31") (pin "2") (pinfunction "2_2") (pintype "passive"))
      (node (ref "U9") (pin "1") (pinfunction "OUT1_1") (pintype "passive"))
      (node (ref "U9") (pin "2") (pinfunction "IN1-_2") (pintype "passive"))
    )
    (net (code "72") (name "Net-(U9B-IN2+)") (class "Default")
      (node (ref "R34") (pin "1") (pinfunction "1_1") (pintype "passive"))
      (node (ref "U9") (pin "5") (pinfunction "IN2+_5") (pintype "passive"))
    )
    (net (code "73") (name "Net-(U9B-IN2-)") (class "Default")
      (node (ref "R35") (pin "2") (pinfunction "2_2") (pintype "passive"))
      (node (ref "U9") (pin "6") (pinfunction "IN2-_6") (pintype "passive"))
      (node (ref "U9") (pin "7") (pinfunction "OUT2_7") (pintype "passive"))
    )
    (net (code "74") (name "Net-(U9C-IN3+)") (class "Default")
      (node (ref "R43") (pin "1") (pinfunction "1_1") (pintype "passive"))
      (node (ref "U9") (pin "10") (pinfunction "IN3+_10") (pintype "passive"))
    )
    (net (code "75") (name "Net-(U9C-IN3-)") (class "Default")
      (node (ref "R44") (pin "2") (pinfunction "2_2") (pintype "passive"))
      (node (ref "U9") (pin "8") (pinfunction "OUT3_8") (pintype "passive"))
      (node (ref "U9") (pin "9") (pinfunction "IN3-_9") (pintype "passive"))
    )
    (net (code "76") (name "Net-(U9D-IN4+)") (class "Default")
      (node (ref "R38") (pin "1") (pinfunction "1_1") (pintype "passive"))
      (node (ref "U9") (pin "12") (pinfunction "IN4+_12") (pintype "passive"))
    )
    (net (code "77") (name "Net-(U9D-IN4-)") (class "Default")
      (node (ref "R39") (pin "2") (pinfunction "2_2") (pintype "passive"))
      (node (ref "U9") (pin "13") (pinfunction "IN4-_13") (pintype "passive"))
      (node (ref "U9") (pin "14") (pinfunction "OUT4_14") (pintype "passive"))
    )
    (net (code "78") (name "Net-(U10A-PH0-OSC_IN)") (class "Default")
      (node (ref "C35") (pin "2") (pinfunction "2_2") (pintype "passive"))
      (node (ref "U10") (pin "5") (pinfunction "PH0-OSC_IN_5") (pintype "bidirectional"))
      (node (ref "X1") (pin "1") (pinfunction "1_1") (pintype "passive"))
    )
    (net (code "79") (name "Net-(U10A-PH1-OSC_OUT)") (class "Default")
      (node (ref "C36") (pin "2") (pinfunction "2_2") (pintype "passive"))
      (node (ref "U10") (pin "6") (pinfunction "PH1-OSC_OUT_6") (pintype "bidirectional"))
      (node (ref "X1") (pin "3") (pinfunction "2_3") (pintype "passive"))
    )
    (net (code "80") (name "Net-(U10A-VCAP1)") (class "Default")
      (node (ref "C38") (pin "2") (pinfunction "2_2") (pintype "passive"))
      (node (ref "U10") (pin "30") (pinfunction "VCAP1_30") (pintype "power_in"))
    )
    (net (code "81") (name "Net-(U11A-IN1+)") (class "Default")
      (node (ref "R49") (pin "1") (pinfunction "1_1") (pintype "passive"))
      (node (ref "U11") (pin "3") (pinfunction "IN1+_3") (pintype "passive"))
    )
    (net (code "82") (name "Net-(U11A-IN1-)") (class "Default")
      (node (ref "R50") (pin "2") (pinfunction "2_2") (pintype "passive"))
      (node (ref "U11") (pin "1") (pinfunction "OUT1_1") (pintype "passive"))
      (node (ref "U11") (pin "2") (pinfunction "IN1-_2") (pintype "passive"))
    )
    (net (code "83") (name "Net-(U11B-IN2+)") (class "Default")
      (node (ref "R54") (pin "1") (pinfunction "1_1") (pintype "passive"))
      (node (ref "U11") (pin "5") (pinfunction "IN2+_5") (pintype "passive"))
    )
    (net (code "84") (name "Net-(U11B-IN2-)") (class "Default")
      (node (ref "R55") (pin "2") (pinfunction "2_2") (pintype "passive"))
      (node (ref "U11") (pin "6") (pinfunction "IN2-_6") (pintype "passive"))
      (node (ref "U11") (pin "7") (pinfunction "OUT2_7") (pintype "passive"))
    )
    (net (code "85") (name "Net-(U11C-IN3+)") (class "Default")
      (node (ref "R69") (pin "1") (pinfunction "1_1") (pintype "passive"))
      (node (ref "U11") (pin "10") (pinfunction "IN3+_10") (pintype "passive"))
    )
    (net (code "86") (name "Net-(U11C-IN3-)") (class "Default")
      (node (ref "R70") (pin "2") (pinfunction "2_2") (pintype "passive"))
      (node (ref "U11") (pin "8") (pinfunction "OUT3_8") (pintype "passive"))
      (node (ref "U11") (pin "9") (pinfunction "IN3-_9") (pintype "passive"))
    )
    (net (code "87") (name "Net-(U11D-IN4+)") (class "Default")
      (node (ref "R60") (pin "1") (pinfunction "1_1") (pintype "passive"))
      (node (ref "U11") (pin "12") (pinfunction "IN4+_12") (pintype "passive"))
    )
    (net (code "88") (name "Net-(U11D-IN4-)") (class "Default")
      (node (ref "R64") (pin "2") (pinfunction "2_2") (pintype "passive"))
      (node (ref "U11") (pin "13") (pinfunction "IN4-_13") (pintype "passive"))
      (node (ref "U11") (pin "14") (pinfunction "OUT4_14") (pintype "passive"))
    )
    (net (code "89") (name "Net-(U12A-IN1+)") (class "Default")
      (node (ref "R73") (pin "1") (pinfunction "1_1") (pintype "passive"))
      (node (ref "U12") (pin "3") (pinfunction "IN1+_3") (pintype "passive"))
    )
    (net (code "90") (name "Net-(U12A-IN1-)") (class "Default")
      (node (ref "R74") (pin "2") (pinfunction "2_2") (pintype "passive"))
      (node (ref "U12") (pin "1") (pinfunction "OUT1_1") (pintype "passive"))
      (node (ref "U12") (pin "2") (pinfunction "IN1-_2") (pintype "passive"))
    )
    (net (code "91") (name "Net-(U12B-IN2+)") (class "Default")
      (node (ref "R77") (pin "1") (pinfunction "1_1") (pintype "passive"))
      (node (ref "U12") (pin "5") (pinfunction "IN2+_5") (pintype "passive"))
    )
    (net (code "92") (name "Net-(U12B-IN2-)") (class "Default")
      (node (ref "R78") (pin "2") (pinfunction "2_2") (pintype "passive"))
      (node (ref "U12") (pin "6") (pinfunction "IN2-_6") (pintype "passive"))
      (node (ref "U12") (pin "7") (pinfunction "OUT2_7") (pintype "passive"))
    )
    (net (code "93") (name "Net-(U12C-IN3+)") (class "Default")
      (node (ref "R85") (pin "1") (pinfunction "1_1") (pintype "passive"))
      (node (ref "U12") (pin "10") (pinfunction "IN3+_10") (pintype "passive"))
    )
    (net (code "94") (name "Net-(U12C-IN3-)") (class "Default")
      (node (ref "R86") (pin "2") (pinfunction "2_2") (pintype "passive"))
      (node (ref "U12") (pin "8") (pinfunction "OUT3_8") (pintype "passive"))
      (node (ref "U12") (pin "9") (pinfunction "IN3-_9") (pintype "passive"))
    )
    (net (code "95") (name "Net-(U12D-IN4+)") (class "Default")
      (node (ref "R81") (pin "1") (pinfunction "1_1") (pintype "passive"))
      (node (ref "U12") (pin "12") (pinfunction "IN4+_12") (pintype "passive"))
    )
    (net (code "96") (name "Net-(U12D-IN4-)") (class "Default")
      (node (ref "R82") (pin "2") (pinfunction "2_2") (pintype "passive"))
      (node (ref "U12") (pin "13") (pinfunction "IN4-_13") (pintype "passive"))
      (node (ref "U12") (pin "14") (pinfunction "OUT4_14") (pintype "passive"))
    )
    (net (code "97") (name "VBAT") (class "Default")
      (node (ref "R59") (pin "2") (pinfunction "2_2") (pintype "passive"))
    )
    (net (code "98") (name "unconnected-(J11-SBU1-PadA8)") (class "Default")
      (node (ref "J11") (pin "A8") (pinfunction "SBU1_A8") (pintype "passive+no_connect"))
    )
    (net (code "99") (name "unconnected-(J11-SBU2-PadB8)") (class "Default")
      (node (ref "J11") (pin "B8") (pinfunction "SBU2_B8") (pintype "passive+no_connect"))
    )
    (net (code "100") (name "unconnected-(U10A-PC14-OSC32_IN-Pad3)") (class "Default")
      (node (ref "U10") (pin "3") (pinfunction "PC14-OSC32_IN_3") (pintype "bidirectional+no_connect"))
    )
    (net (code "101") (name "unconnected-(U10A-PC15-OSC32_OUT-Pad4)") (class "Default")
      (node (ref "U10") (pin "4") (pinfunction "PC15-OSC32_OUT_4") (pintype "bidirectional+no_connect"))
    )
    (net (code "102") (name "unconnected-(U10B-VBAT-Pad1)") (class "Default")
      (node (ref "U10") (pin "1") (pinfunction "VBAT_1") (pintype "power_in+no_connect"))
    )
  )
)
